# PSPS_AVNC_MITCH_2021-03-02.net
KiCad netlist of a schematic drawn in EAGLE
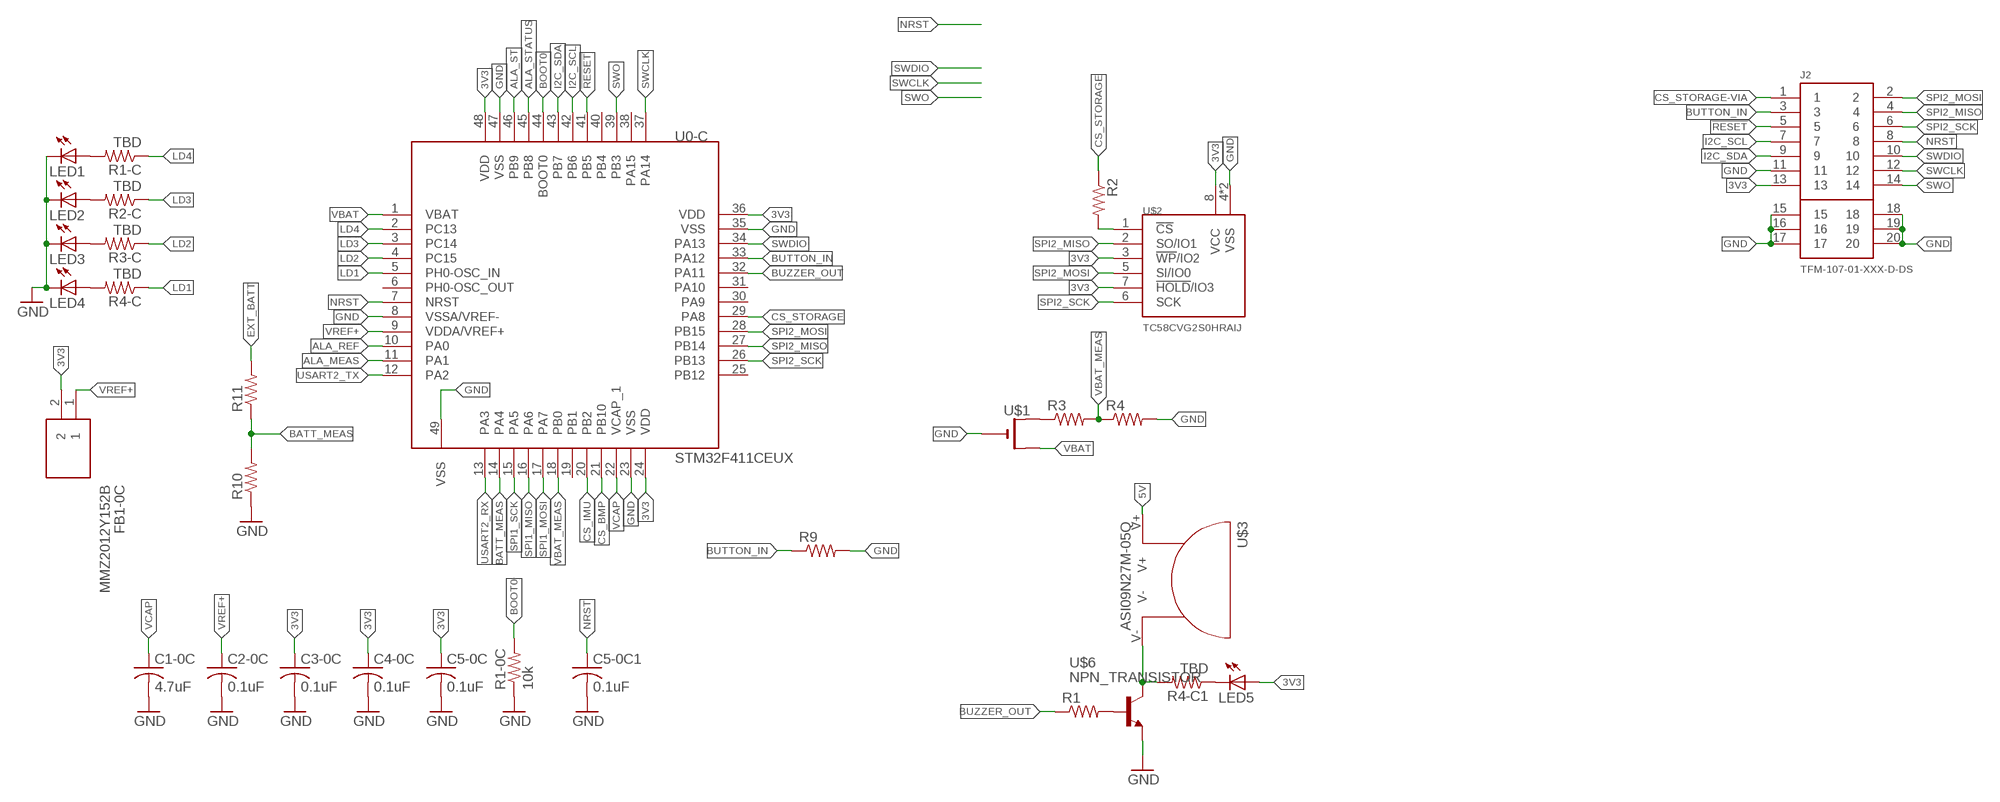
[diagram p0: schematic, sheet 1]
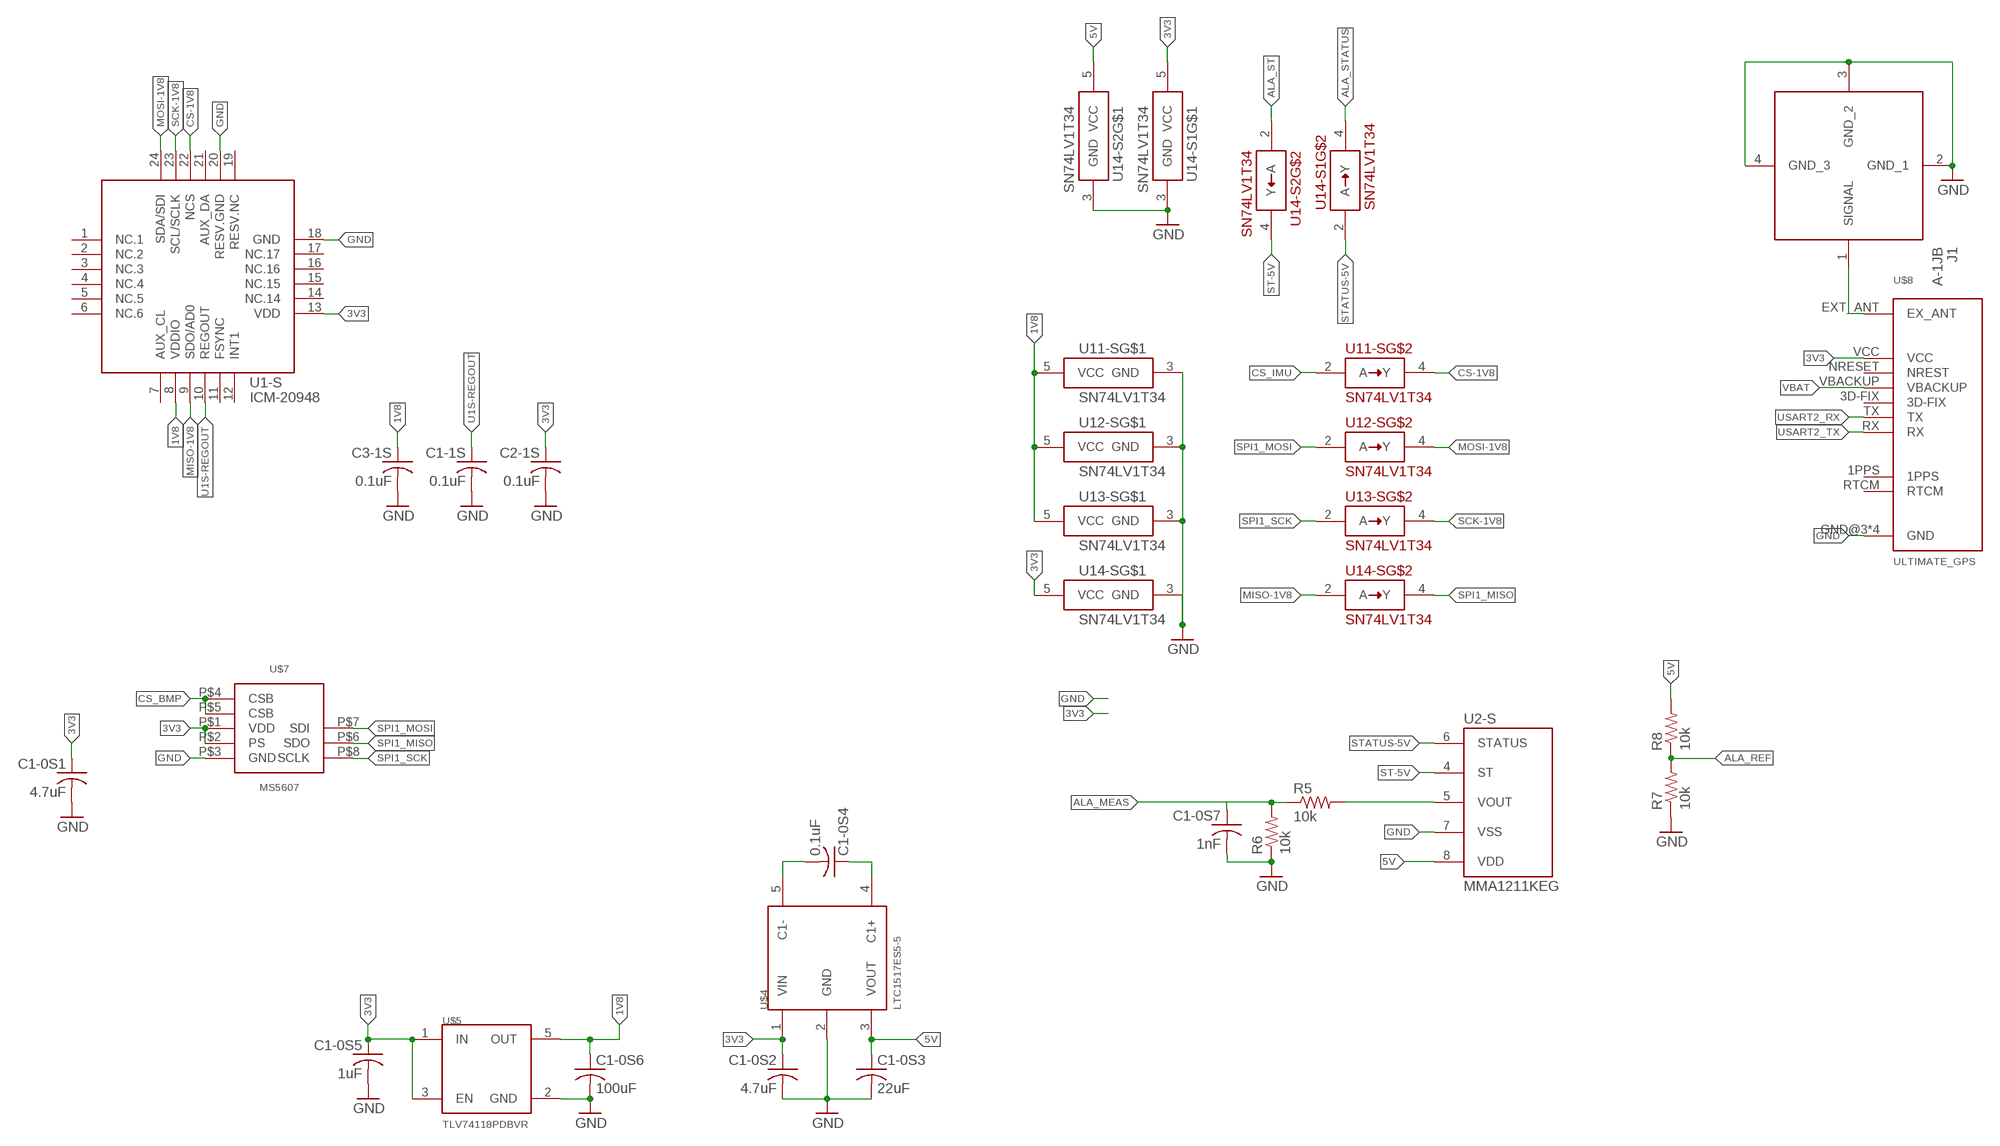
[diagram p1: schematic, sheet 2]

(export (version "E")
  (design (tool "Eeschema 10.0.6"))
  (components
    (comp (ref "C1-0S1")
      (value "4.7uF")
      (footprint "eagle-import:C0805")
      (libsource (lib "eagle-import") (part "C-USC0805"))
    )
    (comp (ref "C1-0S2")
      (value "4.7uF")
      (footprint "eagle-import:C0805")
      (libsource (lib "eagle-import") (part "C-USC0805"))
    )
    (comp (ref "C1-0S3")
      (value "22uF")
      (footprint "eagle-import:C0805")
      (libsource (lib "eagle-import") (part "C-USC0805"))
    )
    (comp (ref "C1-0S4")
      (value "0.1uF")
      (footprint "eagle-import:C0805")
      (libsource (lib "eagle-import") (part "C-USC0805"))
    )
    (comp (ref "C1-0S5")
      (value "1uF")
      (footprint "eagle-import:C0805")
      (libsource (lib "eagle-import") (part "C-USC0805"))
    )
    (comp (ref "C1-0S6")
      (value "100uF")
      (footprint "eagle-import:C0805")
      (libsource (lib "eagle-import") (part "C-USC0805"))
    )
    (comp (ref "C1-0S7")
      (value "1nF")
      (footprint "eagle-import:C0805")
      (libsource (lib "eagle-import") (part "C-USC0805"))
    )
    (comp (ref "C1-1S")
      (value "0.1uF")
      (footprint "eagle-import:C0805")
      (libsource (lib "eagle-import") (part "C-USC0805"))
    )
    (comp (ref "C2-1S")
      (value "0.1uF")
      (footprint "eagle-import:C0805")
      (libsource (lib "eagle-import") (part "C-USC0805"))
    )
    (comp (ref "C3-1S")
      (value "0.1uF")
      (footprint "eagle-import:C0805")
      (libsource (lib "eagle-import") (part "C-USC0805"))
    )
    (comp (ref "J1")
      (value "A-1JB")
      (footprint "eagle-import:A1JB")
      (fields (field (name "MOUSER_PART_NUMBER") "523-A-1JB"))
      (libsource (lib "eagle-import") (part "A-1JB"))
    )
    (comp (ref "R5")
      (value "10k")
      (footprint "eagle-import:R0805")
      (libsource (lib "eagle-import") (part "R-US_R0805"))
    )
    (comp (ref "R6")
      (value "10k")
      (footprint "eagle-import:R0805")
      (libsource (lib "eagle-import") (part "R-US_R0805"))
    )
    (comp (ref "R7")
      (value "10k")
      (footprint "eagle-import:R0805")
      (libsource (lib "eagle-import") (part "R-US_R0805"))
    )
    (comp (ref "R8")
      (value "10k")
      (footprint "eagle-import:R0805")
      (libsource (lib "eagle-import") (part "R-US_R0805"))
    )
    (comp (ref "U$4")
      (value "LTC1517ES5-5")
      (footprint "eagle-import:SOT95P280X145-5N")
      (libsource (lib "eagle-import") (part "LTC1517ES5-5"))
    )
    (comp (ref "U$5")
      (value "TLV74118PDBVR")
      (footprint "eagle-import:SOT95P280X145-5N")
      (libsource (lib "eagle-import") (part "TLV74118PDBVR"))
    )
    (comp (ref "U$7")
      (value "MS5607")
      (footprint "eagle-import:MS5607")
      (libsource (lib "eagle-import") (part "MS5607"))
    )
    (comp (ref "U$8")
      (value "ULTIMATE_GPS")
      (footprint "eagle-import:FGPMMOPA6H")
      (libsource (lib "eagle-import") (part "ULTIMATE_GPS"))
    )
    (comp (ref "U1-S")
      (value "ICM-20948")
      (footprint "eagle-import:QFN40P300X300X105-25T159X175")
      (libsource (lib "eagle-import") (part "ICM-20948"))
    )
    (comp (ref "U2-S")
      (value "MMA1211KEG")
      (footprint "eagle-import:SOIC127P1041X355-16N")
      (libsource (lib "eagle-import") (part "MMA1211KEG"))
    )
    (comp (ref "U11-S")
      (value "SN74LV1T34")
      (footprint "eagle-import:SOT65P210X110-5")
      (libsource (lib "eagle-import") (part "SN74LV1T34"))
    )
    (comp (ref "U12-S")
      (value "SN74LV1T34")
      (footprint "eagle-import:SOT65P210X110-5")
      (libsource (lib "eagle-import") (part "SN74LV1T34"))
    )
    (comp (ref "U13-S")
      (value "SN74LV1T34")
      (footprint "eagle-import:SOT65P210X110-5")
      (libsource (lib "eagle-import") (part "SN74LV1T34"))
    )
    (comp (ref "U14-S")
      (value "SN74LV1T34")
      (footprint "eagle-import:SOT65P210X110-5")
      (libsource (lib "eagle-import") (part "SN74LV1T34"))
    )
    (comp (ref "U14-S1")
      (value "SN74LV1T34")
      (footprint "eagle-import:SOT65P210X110-5")
      (libsource (lib "eagle-import") (part "SN74LV1T34"))
    )
    (comp (ref "U14-S2")
      (value "SN74LV1T34")
      (footprint "eagle-import:SOT65P210X110-5")
      (libsource (lib "eagle-import") (part "SN74LV1T34"))
    )
    (comp (ref "C1-0C")
      (value "4.7uF")
      (footprint "eagle-import:C0805")
      (libsource (lib "eagle-import") (part "C-USC0805"))
    )
    (comp (ref "C2-0C")
      (value "0.1uF")
      (footprint "eagle-import:C0805")
      (libsource (lib "eagle-import") (part "C-USC0805"))
    )
    (comp (ref "C3-0C")
      (value "0.1uF")
      (footprint "eagle-import:C0805")
      (libsource (lib "eagle-import") (part "C-USC0805"))
    )
    (comp (ref "C4-0C")
      (value "0.1uF")
      (footprint "eagle-import:C0805")
      (libsource (lib "eagle-import") (part "C-USC0805"))
    )
    (comp (ref "C5-0C")
      (value "0.1uF")
      (footprint "eagle-import:C0805")
      (libsource (lib "eagle-import") (part "C-USC0805"))
    )
    (comp (ref "C5-0C1")
      (value "0.1uF")
      (footprint "eagle-import:C0805")
      (libsource (lib "eagle-import") (part "C-USC0805"))
    )
    (comp (ref "FB1-0C")
      (value "MMZ2012Y152B")
      (footprint "eagle-import:BEADC2012X105N")
      (fields (field (name "MOUSER_PART_NUMBER") "810-MMZ2012Y152B"))
      (libsource (lib "eagle-import") (part "MMZ2012Y152B"))
    )
    (comp (ref "J2")
      (value "TFM-107-01-XXX-D-DS")
      (footprint "eagle-import:TFM-107-01-XXX-D-DS")
      (libsource (lib "eagle-import") (part "TFM-107-01-XXX-D-DS"))
    )
    (comp (ref "LED1")
      (value "LEDCHIPLED_0805")
      (footprint "eagle-import:CHIPLED_0805")
      (libsource (lib "eagle-import") (part "LEDCHIPLED_0805"))
    )
    (comp (ref "LED2")
      (value "LEDCHIPLED_0805")
      (footprint "eagle-import:CHIPLED_0805")
      (libsource (lib "eagle-import") (part "LEDCHIPLED_0805"))
    )
    (comp (ref "LED3")
      (value "LEDCHIPLED_0805")
      (footprint "eagle-import:CHIPLED_0805")
      (libsource (lib "eagle-import") (part "LEDCHIPLED_0805"))
    )
    (comp (ref "LED4")
      (value "LEDCHIPLED_0805")
      (footprint "eagle-import:CHIPLED_0805")
      (libsource (lib "eagle-import") (part "LEDCHIPLED_0805"))
    )
    (comp (ref "LED5")
      (value "LEDCHIPLED_0805")
      (footprint "eagle-import:CHIPLED_0805")
      (libsource (lib "eagle-import") (part "LEDCHIPLED_0805"))
    )
    (comp (ref "R1")
      (value "R-US_R0805")
      (footprint "eagle-import:R0805")
      (libsource (lib "eagle-import") (part "R-US_R0805"))
    )
    (comp (ref "R1-0C")
      (value "10k")
      (footprint "eagle-import:R0805")
      (libsource (lib "eagle-import") (part "R-US_R0805"))
    )
    (comp (ref "R1-C")
      (value "TBD")
      (footprint "eagle-import:R0805")
      (libsource (lib "eagle-import") (part "R-US_R0805"))
    )
    (comp (ref "R2")
      (value "R-US_R0805")
      (footprint "eagle-import:R0805")
      (libsource (lib "eagle-import") (part "R-US_R0805"))
    )
    (comp (ref "R2-C")
      (value "TBD")
      (footprint "eagle-import:R0805")
      (libsource (lib "eagle-import") (part "R-US_R0805"))
    )
    (comp (ref "R3")
      (value "R-US_R0805")
      (footprint "eagle-import:R0805")
      (libsource (lib "eagle-import") (part "R-US_R0805"))
    )
    (comp (ref "R3-C")
      (value "TBD")
      (footprint "eagle-import:R0805")
      (libsource (lib "eagle-import") (part "R-US_R0805"))
    )
    (comp (ref "R4")
      (value "R-US_R0805")
      (footprint "eagle-import:R0805")
      (libsource (lib "eagle-import") (part "R-US_R0805"))
    )
    (comp (ref "R4-C")
      (value "TBD")
      (footprint "eagle-import:R0805")
      (libsource (lib "eagle-import") (part "R-US_R0805"))
    )
    (comp (ref "R4-C1")
      (value "TBD")
      (footprint "eagle-import:R0805")
      (libsource (lib "eagle-import") (part "R-US_R0805"))
    )
    (comp (ref "R9")
      (value "R-US_R0805")
      (footprint "eagle-import:R0805")
      (libsource (lib "eagle-import") (part "R-US_R0805"))
    )
    (comp (ref "R10")
      (value "R-US_R0805")
      (footprint "eagle-import:R0805")
      (libsource (lib "eagle-import") (part "R-US_R0805"))
    )
    (comp (ref "R11")
      (value "R-US_R0805")
      (footprint "eagle-import:R0805")
      (libsource (lib "eagle-import") (part "R-US_R0805"))
    )
    (comp (ref "U$1")
      (value "CR1220SMT")
      (footprint "eagle-import:CR1220-SMD")
      (libsource (lib "eagle-import") (part "CR1220SMT"))
    )
    (comp (ref "U$2")
      (value "TC58CVG2S0HRAIJ")
      (footprint "eagle-import:SON127P800X600X80-9T350X440N")
      (libsource (lib "eagle-import") (part "TC58CVG2S0HRAIJ"))
    )
    (comp (ref "U$3")
      (value "ASI09N27M-05Q")
      (footprint "eagle-import:ASI09N27M-05Q")
      (libsource (lib "eagle-import") (part "ASI09N27M-05Q"))
    )
    (comp (ref "U$6")
      (value "NPN_TRANSISTOR")
      (footprint "eagle-import:SOT23")
      (libsource (lib "eagle-import") (part "NPN_TRANSISTOR"))
    )
    (comp (ref "U0-C")
      (value "STM32F411CEUX")
      (footprint "eagle-import:QFN50P700X700X50-49T560N")
      (libsource (lib "eagle-import") (part "STM32F411CEUX"))
    )
  )
  (nets
    (net (code "1") (name "1V8") (class "Default")
      (node (ref "C1-0S6") (pin "1") (pinfunction "1_1") (pintype "passive"))
      (node (ref "C3-1S") (pin "1") (pinfunction "1_1") (pintype "passive"))
      (node (ref "U$5") (pin "5") (pinfunction "OUT_5") (pintype "bidirectional"))
      (node (ref "U1-S") (pin "8") (pinfunction "VDDIO_8") (pintype "bidirectional"))
      (node (ref "U11-S") (pin "5") (pinfunction "VCC_5") (pintype "bidirectional"))
      (node (ref "U12-S") (pin "5") (pinfunction "VCC_5") (pintype "bidirectional"))
      (node (ref "U13-S") (pin "5") (pinfunction "VCC_5") (pintype "bidirectional"))
    )
    (net (code "2") (name "3V3") (class "Default")
      (node (ref "C1-0S1") (pin "1") (pinfunction "1_1") (pintype "passive"))
      (node (ref "C1-0S2") (pin "1") (pinfunction "1_1") (pintype "passive"))
      (node (ref "C1-0S5") (pin "1") (pinfunction "1_1") (pintype "passive"))
      (node (ref "C2-1S") (pin "1") (pinfunction "1_1") (pintype "passive"))
      (node (ref "C3-0C") (pin "1") (pinfunction "1_1") (pintype "passive"))
      (node (ref "C4-0C") (pin "1") (pinfunction "1_1") (pintype "passive"))
      (node (ref "C5-0C") (pin "1") (pinfunction "1_1") (pintype "passive"))
      (node (ref "FB1-0C") (pin "2") (pinfunction "2_2") (pintype "bidirectional"))
      (node (ref "J2") (pin "13") (pinfunction "13_13") (pintype "bidirectional"))
      (node (ref "LED5") (pin "A") (pinfunction "A_A") (pintype "passive"))
      (node (ref "U$2") (pin "3") (pinfunction "~{WP}/IO2_3") (pintype "bidirectional"))
      (node (ref "U$2") (pin "7") (pinfunction "~{HOLD}/IO3_7") (pintype "bidirectional"))
      (node (ref "U$2") (pin "8") (pinfunction "VCC_8") (pintype "bidirectional"))
      (node (ref "U$4") (pin "1") (pinfunction "VIN_1") (pintype "bidirectional"))
      (node (ref "U$5") (pin "1") (pinfunction "IN_1") (pintype "bidirectional"))
      (node (ref "U$5") (pin "3") (pinfunction "EN_3") (pintype "bidirectional"))
      (node (ref "U$7") (pin "P$1") (pinfunction "VDD_P$1") (pintype "bidirectional"))
      (node (ref "U$7") (pin "P$2") (pinfunction "PS_P$2") (pintype "bidirectional"))
      (node (ref "U$8") (pin "VCC") (pinfunction "VCC_VCC") (pintype "bidirectional"))
      (node (ref "U0-C") (pin "24") (pinfunction "VDD_24") (pintype "bidirectional"))
      (node (ref "U0-C") (pin "36") (pinfunction "VDD_36") (pintype "bidirectional"))
      (node (ref "U0-C") (pin "48") (pinfunction "VDD_48") (pintype "bidirectional"))
      (node (ref "U1-S") (pin "13") (pinfunction "VDD_13") (pintype "bidirectional"))
      (node (ref "U14-S") (pin "5") (pinfunction "VCC_5") (pintype "bidirectional"))
      (node (ref "U14-S1") (pin "5") (pinfunction "VCC_5") (pintype "bidirectional"))
    )
    (net (code "3") (name "5V") (class "Default")
      (node (ref "C1-0S3") (pin "1") (pinfunction "1_1") (pintype "passive"))
      (node (ref "R8") (pin "2") (pinfunction "2_2") (pintype "passive"))
      (node (ref "U$3") (pin "V+") (pinfunction "V+_V+") (pintype "bidirectional"))
      (node (ref "U$4") (pin "3") (pinfunction "VOUT_3") (pintype "bidirectional"))
      (node (ref "U14-S2") (pin "5") (pinfunction "VCC_5") (pintype "bidirectional"))
      (node (ref "U2-S") (pin "8") (pinfunction "VDD_8") (pintype "bidirectional"))
    )
    (net (code "4") (name "ALA_MEAS") (class "Default")
      (node (ref "C1-0S7") (pin "1") (pinfunction "1_1") (pintype "passive"))
      (node (ref "R5") (pin "1") (pinfunction "1_1") (pintype "passive"))
      (node (ref "R6") (pin "2") (pinfunction "2_2") (pintype "passive"))
      (node (ref "U0-C") (pin "11") (pinfunction "PA1_11") (pintype "bidirectional"))
    )
    (net (code "5") (name "ALA_REF") (class "Default")
      (node (ref "R7") (pin "2") (pinfunction "2_2") (pintype "passive"))
      (node (ref "R8") (pin "1") (pinfunction "1_1") (pintype "passive"))
      (node (ref "U0-C") (pin "10") (pinfunction "PA0_10") (pintype "bidirectional"))
    )
    (net (code "6") (name "ALA_ST") (class "Default")
      (node (ref "U0-C") (pin "46") (pinfunction "PB9_46") (pintype "bidirectional"))
      (node (ref "U14-S2") (pin "2") (pinfunction "A_2") (pintype "bidirectional"))
    )
    (net (code "7") (name "ALA_STATUS") (class "Default")
      (node (ref "U0-C") (pin "45") (pinfunction "PB8_45") (pintype "bidirectional"))
      (node (ref "U14-S1") (pin "4") (pinfunction "Y_4") (pintype "bidirectional"))
    )
    (net (code "8") (name "BATT_MEAS") (class "Default")
      (node (ref "R10") (pin "2") (pinfunction "2_2") (pintype "passive"))
      (node (ref "R11") (pin "1") (pinfunction "1_1") (pintype "passive"))
      (node (ref "U0-C") (pin "14") (pinfunction "PA4_14") (pintype "bidirectional"))
    )
    (net (code "9") (name "BOOT0") (class "Default")
      (node (ref "R1-0C") (pin "2") (pinfunction "2_2") (pintype "passive"))
      (node (ref "U0-C") (pin "44") (pinfunction "BOOT0_44") (pintype "bidirectional"))
    )
    (net (code "10") (name "BUTTON_IN") (class "Default")
      (node (ref "J2") (pin "3") (pinfunction "3_3") (pintype "bidirectional"))
      (node (ref "R9") (pin "1") (pinfunction "1_1") (pintype "passive"))
      (node (ref "U0-C") (pin "33") (pinfunction "PA12_33") (pintype "bidirectional"))
    )
    (net (code "11") (name "BUZZER_OUT") (class "Default")
      (node (ref "R1") (pin "1") (pinfunction "1_1") (pintype "passive"))
      (node (ref "U0-C") (pin "32") (pinfunction "PA11_32") (pintype "bidirectional"))
    )
    (net (code "12") (name "CS-1V8") (class "Default")
      (node (ref "U1-S") (pin "22") (pinfunction "NCS_22") (pintype "bidirectional"))
      (node (ref "U11-S") (pin "4") (pinfunction "Y_4") (pintype "bidirectional"))
    )
    (net (code "13") (name "CS_BMP") (class "Default")
      (node (ref "U$7") (pin "P$4") (pinfunction "CSB_P$4") (pintype "bidirectional"))
      (node (ref "U$7") (pin "P$5") (pinfunction "CSB_P$5") (pintype "bidirectional"))
      (node (ref "U0-C") (pin "21") (pinfunction "PB10_21") (pintype "bidirectional"))
    )
    (net (code "14") (name "CS_IMU") (class "Default")
      (node (ref "U0-C") (pin "20") (pinfunction "PB2_20") (pintype "bidirectional"))
      (node (ref "U11-S") (pin "2") (pinfunction "A_2") (pintype "bidirectional"))
    )
    (net (code "15") (name "CS_STORAGE") (class "Default")
      (node (ref "R2") (pin "1") (pinfunction "1_1") (pintype "passive"))
      (node (ref "U0-C") (pin "29") (pinfunction "PA8_29") (pintype "bidirectional"))
    )
    (net (code "16") (name "CS_STORAGE-VIA") (class "Default")
      (node (ref "J2") (pin "1") (pinfunction "1_1") (pintype "bidirectional"))
      (node (ref "R2") (pin "2") (pinfunction "2_2") (pintype "passive"))
      (node (ref "U$2") (pin "1") (pinfunction "~{CS}_1") (pintype "bidirectional"))
    )
    (net (code "17") (name "EXT_BATT") (class "Default")
      (node (ref "R11") (pin "2") (pinfunction "2_2") (pintype "passive"))
    )
    (net (code "18") (name "GND") (class "Default")
      (node (ref "C1-0C") (pin "2") (pinfunction "2_2") (pintype "passive"))
      (node (ref "C1-0S1") (pin "2") (pinfunction "2_2") (pintype "passive"))
      (node (ref "C1-0S2") (pin "2") (pinfunction "2_2") (pintype "passive"))
      (node (ref "C1-0S3") (pin "2") (pinfunction "2_2") (pintype "passive"))
      (node (ref "C1-0S5") (pin "2") (pinfunction "2_2") (pintype "passive"))
      (node (ref "C1-0S6") (pin "2") (pinfunction "2_2") (pintype "passive"))
      (node (ref "C1-0S7") (pin "2") (pinfunction "2_2") (pintype "passive"))
      (node (ref "C1-1S") (pin "2") (pinfunction "2_2") (pintype "passive"))
      (node (ref "C2-0C") (pin "2") (pinfunction "2_2") (pintype "passive"))
      (node (ref "C2-1S") (pin "2") (pinfunction "2_2") (pintype "passive"))
      (node (ref "C3-0C") (pin "2") (pinfunction "2_2") (pintype "passive"))
      (node (ref "C3-1S") (pin "2") (pinfunction "2_2") (pintype "passive"))
      (node (ref "C4-0C") (pin "2") (pinfunction "2_2") (pintype "passive"))
      (node (ref "C5-0C") (pin "2") (pinfunction "2_2") (pintype "passive"))
      (node (ref "C5-0C1") (pin "2") (pinfunction "2_2") (pintype "passive"))
      (node (ref "J1") (pin "2") (pinfunction "GND_1_2") (pintype "bidirectional"))
      (node (ref "J1") (pin "3") (pinfunction "GND_2_3") (pintype "bidirectional"))
      (node (ref "J1") (pin "4") (pinfunction "GND_3_4") (pintype "bidirectional"))
      (node (ref "J2") (pin "11") (pinfunction "11_11") (pintype "bidirectional"))
      (node (ref "J2") (pin "15") (pinfunction "15_15") (pintype "bidirectional"))
      (node (ref "J2") (pin "16") (pinfunction "16_16") (pintype "bidirectional"))
      (node (ref "J2") (pin "17") (pinfunction "17_17") (pintype "bidirectional"))
      (node (ref "J2") (pin "18") (pinfunction "18_18") (pintype "bidirectional"))
      (node (ref "J2") (pin "19") (pinfunction "19_19") (pintype "bidirectional"))
      (node (ref "J2") (pin "20") (pinfunction "20_20") (pintype "bidirectional"))
      (node (ref "LED1") (pin "C") (pinfunction "C_C") (pintype "passive"))
      (node (ref "LED2") (pin "C") (pinfunction "C_C") (pintype "passive"))
      (node (ref "LED3") (pin "C") (pinfunction "C_C") (pintype "passive"))
      (node (ref "LED4") (pin "C") (pinfunction "C_C") (pintype "passive"))
      (node (ref "R1-0C") (pin "1") (pinfunction "1_1") (pintype "passive"))
      (node (ref "R10") (pin "1") (pinfunction "1_1") (pintype "passive"))
      (node (ref "R4") (pin "2") (pinfunction "2_2") (pintype "passive"))
      (node (ref "R6") (pin "1") (pinfunction "1_1") (pintype "passive"))
      (node (ref "R7") (pin "1") (pinfunction "1_1") (pintype "passive"))
      (node (ref "R9") (pin "2") (pinfunction "2_2") (pintype "passive"))
      (node (ref "U$1") (pin "-") (pinfunction "-_-") (pintype "passive"))
      (node (ref "U$2") (pin "4") (pinfunction "VSS_4") (pintype "bidirectional"))
      (node (ref "U$2") (pin "9") (pinfunction "VSS_9") (pintype "bidirectional"))
      (node (ref "U$4") (pin "2") (pinfunction "GND_2") (pintype "bidirectional"))
      (node (ref "U$5") (pin "2") (pinfunction "GND_2") (pintype "bidirectional"))
      (node (ref "U$6") (pin "3") (pinfunction "E_3") (pintype "passive"))
      (node (ref "U$7") (pin "P$3") (pinfunction "GND_P$3") (pintype "bidirectional"))
      (node (ref "U$8") (pin "GND@12") (pinfunction "GND_GND@12") (pintype "bidirectional"))
      (node (ref "U$8") (pin "GND@19") (pinfunction "GND_GND@19") (pintype "bidirectional"))
      (node (ref "U$8") (pin "GND@3") (pinfunction "GND_GND@3") (pintype "bidirectional"))
      (node (ref "U$8") (pin "GND@8") (pinfunction "GND_GND@8") (pintype "bidirectional"))
      (node (ref "U0-C") (pin "23") (pinfunction "VSS_23") (pintype "bidirectional"))
      (node (ref "U0-C") (pin "35") (pinfunction "VSS_35") (pintype "bidirectional"))
      (node (ref "U0-C") (pin "47") (pinfunction "VSS_47") (pintype "bidirectional"))
      (node (ref "U0-C") (pin "49") (pinfunction "VSS_49") (pintype "bidirectional"))
      (node (ref "U0-C") (pin "8") (pinfunction "VSSA/VREF-_8") (pintype "bidirectional"))
      (node (ref "U1-S") (pin "18") (pinfunction "GND_18") (pintype "bidirectional"))
      (node (ref "U1-S") (pin "20") (pinfunction "RESV.GND_20") (pintype "bidirectional"))
      (node (ref "U11-S") (pin "3") (pinfunction "GND_3") (pintype "bidirectional"))
      (node (ref "U12-S") (pin "3") (pinfunction "GND_3") (pintype "bidirectional"))
      (node (ref "U13-S") (pin "3") (pinfunction "GND_3") (pintype "bidirectional"))
      (node (ref "U14-S") (pin "3") (pinfunction "GND_3") (pintype "bidirectional"))
      (node (ref "U14-S1") (pin "3") (pinfunction "GND_3") (pintype "bidirectional"))
      (node (ref "U14-S2") (pin "3") (pinfunction "GND_3") (pintype "bidirectional"))
      (node (ref "U2-S") (pin "7") (pinfunction "VSS_7") (pintype "bidirectional"))
    )
    (net (code "19") (name "I2C_SCL") (class "Default")
      (node (ref "J2") (pin "7") (pinfunction "7_7") (pintype "bidirectional"))
      (node (ref "U0-C") (pin "42") (pinfunction "PB6_42") (pintype "bidirectional"))
    )
    (net (code "20") (name "I2C_SDA") (class "Default")
      (node (ref "J2") (pin "9") (pinfunction "9_9") (pintype "bidirectional"))
      (node (ref "U0-C") (pin "43") (pinfunction "PB7_43") (pintype "bidirectional"))
    )
    (net (code "21") (name "LD1") (class "Default")
      (node (ref "R4-C") (pin "1") (pinfunction "1_1") (pintype "passive"))
      (node (ref "U0-C") (pin "5") (pinfunction "PH0-OSC_IN_5") (pintype "bidirectional"))
    )
    (net (code "22") (name "LD2") (class "Default")
      (node (ref "R3-C") (pin "1") (pinfunction "1_1") (pintype "passive"))
      (node (ref "U0-C") (pin "4") (pinfunction "PC15_4") (pintype "bidirectional"))
    )
    (net (code "23") (name "LD3") (class "Default")
      (node (ref "R2-C") (pin "1") (pinfunction "1_1") (pintype "passive"))
      (node (ref "U0-C") (pin "3") (pinfunction "PC14_3") (pintype "bidirectional"))
    )
    (net (code "24") (name "LD4") (class "Default")
      (node (ref "R1-C") (pin "1") (pinfunction "1_1") (pintype "passive"))
      (node (ref "U0-C") (pin "2") (pinfunction "PC13_2") (pintype "bidirectional"))
    )
    (net (code "25") (name "MISO-1V8") (class "Default")
      (node (ref "U1-S") (pin "9") (pinfunction "SDO/AD0_9") (pintype "bidirectional"))
      (node (ref "U14-S") (pin "2") (pinfunction "A_2") (pintype "bidirectional"))
    )
    (net (code "26") (name "MOSI-1V8") (class "Default")
      (node (ref "U1-S") (pin "24") (pinfunction "SDA/SDI_24") (pintype "bidirectional"))
      (node (ref "U12-S") (pin "4") (pinfunction "Y_4") (pintype "bidirectional"))
    )
    (net (code "27") (name "NRST") (class "Default")
      (node (ref "C5-0C1") (pin "1") (pinfunction "1_1") (pintype "passive"))
      (node (ref "J2") (pin "8") (pinfunction "8_8") (pintype "bidirectional"))
      (node (ref "U0-C") (pin "7") (pinfunction "NRST_7") (pintype "bidirectional"))
    )
    (net (code "28") (name "Net-(J1-SIGNAL)") (class "Default")
      (node (ref "J1") (pin "1") (pinfunction "SIGNAL_1") (pintype "bidirectional"))
      (node (ref "U$8") (pin "EXT_ANT") (pinfunction "EX_ANT_EXT_ANT") (pintype "bidirectional"))
    )
    (net (code "29") (name "Net-(LED1-PadA)") (class "Default")
      (node (ref "LED1") (pin "A") (pinfunction "A_A") (pintype "passive"))
      (node (ref "R1-C") (pin "2") (pinfunction "2_2") (pintype "passive"))
    )
    (net (code "30") (name "Net-(LED2-PadA)") (class "Default")
      (node (ref "LED2") (pin "A") (pinfunction "A_A") (pintype "passive"))
      (node (ref "R2-C") (pin "2") (pinfunction "2_2") (pintype "passive"))
    )
    (net (code "31") (name "Net-(LED3-PadA)") (class "Default")
      (node (ref "LED3") (pin "A") (pinfunction "A_A") (pintype "passive"))
      (node (ref "R3-C") (pin "2") (pinfunction "2_2") (pintype "passive"))
    )
    (net (code "32") (name "Net-(LED4-PadA)") (class "Default")
      (node (ref "LED4") (pin "A") (pinfunction "A_A") (pintype "passive"))
      (node (ref "R4-C") (pin "2") (pinfunction "2_2") (pintype "passive"))
    )
    (net (code "33") (name "Net-(LED5-PadC)") (class "Default")
      (node (ref "LED5") (pin "C") (pinfunction "C_C") (pintype "passive"))
      (node (ref "R4-C1") (pin "1") (pinfunction "1_1") (pintype "passive"))
    )
    (net (code "34") (name "Net-(U$1-+)") (class "Default")
      (node (ref "R3") (pin "1") (pinfunction "1_1") (pintype "passive"))
      (node (ref "U$1") (pin "+$1") (pinfunction "+_+$1") (pintype "passive"))
    )
    (net (code "35") (name "Net-(U$4-C1+)") (class "Default")
      (node (ref "C1-0S4") (pin "1") (pinfunction "1_1") (pintype "passive"))
      (node (ref "U$4") (pin "4") (pinfunction "C1+_4") (pintype "bidirectional"))
    )
    (net (code "36") (name "Net-(U$4-C1-)") (class "Default")
      (node (ref "C1-0S4") (pin "2") (pinfunction "2_2") (pintype "passive"))
      (node (ref "U$4") (pin "5") (pinfunction "C1-_5") (pintype "bidirectional"))
    )
    (net (code "37") (name "Net-(U$6-B)") (class "Default")
      (node (ref "R1") (pin "2") (pinfunction "2_2") (pintype "passive"))
      (node (ref "U$6") (pin "1") (pinfunction "B_1") (pintype "passive"))
    )
    (net (code "38") (name "Net-(U$6-C)") (class "Default")
      (node (ref "R4-C1") (pin "2") (pinfunction "2_2") (pintype "passive"))
      (node (ref "U$3") (pin "V-") (pinfunction "V-_V-") (pintype "bidirectional"))
      (node (ref "U$6") (pin "2") (pinfunction "C_2") (pintype "passive"))
    )
    (net (code "39") (name "Net-(U2-S-VOUT)") (class "Default")
      (node (ref "R5") (pin "2") (pinfunction "2_2") (pintype "passive"))
      (node (ref "U2-S") (pin "5") (pinfunction "VOUT_5") (pintype "bidirectional"))
    )
    (net (code "40") (name "SCK-1V8") (class "Default")
      (node (ref "U1-S") (pin "23") (pinfunction "SCL/SCLK_23") (pintype "bidirectional"))
      (node (ref "U13-S") (pin "4") (pinfunction "Y_4") (pintype "bidirectional"))
    )
    (net (code "41") (name "SPI1_MISO") (class "Default")
      (node (ref "U$7") (pin "P$6") (pinfunction "SDO_P$6") (pintype "bidirectional"))
      (node (ref "U0-C") (pin "16") (pinfunction "PA6_16") (pintype "bidirectional"))
      (node (ref "U14-S") (pin "4") (pinfunction "Y_4") (pintype "bidirectional"))
    )
    (net (code "42") (name "SPI1_MOSI") (class "Default")
      (node (ref "U$7") (pin "P$7") (pinfunction "SDI_P$7") (pintype "bidirectional"))
      (node (ref "U0-C") (pin "17") (pinfunction "PA7_17") (pintype "bidirectional"))
      (node (ref "U12-S") (pin "2") (pinfunction "A_2") (pintype "bidirectional"))
    )
    (net (code "43") (name "SPI1_SCK") (class "Default")
      (node (ref "U$7") (pin "P$8") (pinfunction "SCLK_P$8") (pintype "bidirectional"))
      (node (ref "U0-C") (pin "15") (pinfunction "PA5_15") (pintype "bidirectional"))
      (node (ref "U13-S") (pin "2") (pinfunction "A_2") (pintype "bidirectional"))
    )
    (net (code "44") (name "SPI2_MISO") (class "Default")
      (node (ref "J2") (pin "4") (pinfunction "4_4") (pintype "bidirectional"))
      (node (ref "U$2") (pin "2") (pinfunction "SO/IO1_2") (pintype "bidirectional"))
      (node (ref "U0-C") (pin "27") (pinfunction "PB14_27") (pintype "bidirectional"))
    )
    (net (code "45") (name "SPI2_MOSI") (class "Default")
      (node (ref "J2") (pin "2") (pinfunction "2_2") (pintype "bidirectional"))
      (node (ref "U$2") (pin "5") (pinfunction "SI/IO0_5") (pintype "bidirectional"))
      (node (ref "U0-C") (pin "28") (pinfunction "PB15_28") (pintype "bidirectional"))
    )
    (net (code "46") (name "SPI2_SCK") (class "Default")
      (node (ref "J2") (pin "6") (pinfunction "6_6") (pintype "bidirectional"))
      (node (ref "U$2") (pin "6") (pinfunction "SCK_6") (pintype "bidirectional"))
      (node (ref "U0-C") (pin "26") (pinfunction "PB13_26") (pintype "bidirectional"))
    )
    (net (code "47") (name "ST-5V") (class "Default")
      (node (ref "U14-S2") (pin "4") (pinfunction "Y_4") (pintype "bidirectional"))
      (node (ref "U2-S") (pin "4") (pinfunction "ST_4") (pintype "bidirectional"))
    )
    (net (code "48") (name "STATUS-5V") (class "Default")
      (node (ref "U14-S1") (pin "2") (pinfunction "A_2") (pintype "bidirectional"))
      (node (ref "U2-S") (pin "6") (pinfunction "STATUS_6") (pintype "bidirectional"))
    )
    (net (code "49") (name "SWCLK") (class "Default")
      (node (ref "J2") (pin "12") (pinfunction "12_12") (pintype "bidirectional"))
      (node (ref "U0-C") (pin "37") (pinfunction "PA14_37") (pintype "bidirectional"))
    )
    (net (code "50") (name "SWDIO") (class "Default")
      (node (ref "J2") (pin "10") (pinfunction "10_10") (pintype "bidirectional"))
      (node (ref "U0-C") (pin "34") (pinfunction "PA13_34") (pintype "bidirectional"))
    )
    (net (code "51") (name "SWO") (class "Default")
      (node (ref "J2") (pin "14") (pinfunction "14_14") (pintype "bidirectional"))
      (node (ref "U0-C") (pin "39") (pinfunction "PB3_39") (pintype "bidirectional"))
    )
    (net (code "52") (name "U1S-REGOUT") (class "Default")
      (node (ref "C1-1S") (pin "1") (pinfunction "1_1") (pintype "passive"))
      (node (ref "U1-S") (pin "10") (pinfunction "REGOUT_10") (pintype "bidirectional"))
    )
    (net (code "53") (name "USART2_RX") (class "Default")
      (node (ref "U$8") (pin "TX") (pinfunction "TX_TX") (pintype "bidirectional"))
      (node (ref "U0-C") (pin "13") (pinfunction "PA3_13") (pintype "bidirectional"))
    )
    (net (code "54") (name "USART2_TX") (class "Default")
      (node (ref "U$8") (pin "RX") (pinfunction "RX_RX") (pintype "bidirectional"))
      (node (ref "U0-C") (pin "12") (pinfunction "PA2_12") (pintype "bidirectional"))
    )
    (net (code "55") (name "VBAT") (class "Default")
      (node (ref "U$1") (pin "+$2") (pinfunction "+1_+$2") (pintype "passive"))
      (node (ref "U$8") (pin "VBACKUP") (pinfunction "VBACKUP_VBACKUP") (pintype "bidirectional"))
      (node (ref "U0-C") (pin "1") (pinfunction "VBAT_1") (pintype "bidirectional"))
    )
    (net (code "56") (name "VBAT_MEAS") (class "Default")
      (node (ref "R3") (pin "2") (pinfunction "2_2") (pintype "passive"))
      (node (ref "R4") (pin "1") (pinfunction "1_1") (pintype "passive"))
      (node (ref "U0-C") (pin "18") (pinfunction "PB0_18") (pintype "bidirectional"))
    )
    (net (code "57") (name "VCAP") (class "Default")
      (node (ref "C1-0C") (pin "1") (pinfunction "1_1") (pintype "passive"))
      (node (ref "U0-C") (pin "22") (pinfunction "VCAP_1_22") (pintype "bidirectional"))
    )
    (net (code "58") (name "VREF+") (class "Default")
      (node (ref "C2-0C") (pin "1") (pinfunction "1_1") (pintype "passive"))
      (node (ref "FB1-0C") (pin "1") (pinfunction "1_1") (pintype "bidirectional"))
      (node (ref "U0-C") (pin "9") (pinfunction "VDDA/VREF+_9") (pintype "bidirectional"))
    )
    (net (code "59") (name "unconnected-(U$8-NREST-PadNRESET)") (class "Default")
      (node (ref "U$8") (pin "NRESET") (pinfunction "NREST_NRESET") (pintype "bidirectional"))
    )
    (net (code "60") (name "unconnected-(U$8-Pad1PPS)") (class "Default")
      (node (ref "U$8") (pin "1PPS") (pinfunction "1PPS_1PPS") (pintype "bidirectional"))
    )
    (net (code "61") (name "unconnected-(U$8-Pad3D-FIX)") (class "Default")
      (node (ref "U$8") (pin "3D-FIX") (pinfunction "3D-FIX_3D-FIX") (pintype "bidirectional"))
    )
    (net (code "62") (name "unconnected-(U$8-PadRTCM)") (class "Default")
      (node (ref "U$8") (pin "RTCM") (pinfunction "RTCM_RTCM") (pintype "bidirectional"))
    )
    (net (code "63") (name "unconnected-(U0-C-PA9-Pad30)") (class "Default")
      (node (ref "U0-C") (pin "30") (pinfunction "PA9_30") (pintype "bidirectional"))
    )
    (net (code "64") (name "unconnected-(U0-C-PA10-Pad31)") (class "Default")
      (node (ref "U0-C") (pin "31") (pinfunction "PA10_31") (pintype "bidirectional"))
    )
    (net (code "65") (name "unconnected-(U0-C-PA15-Pad38)") (class "Default")
      (node (ref "U0-C") (pin "38") (pinfunction "PA15_38") (pintype "bidirectional"))
    )
    (net (code "66") (name "unconnected-(U0-C-PB1-Pad19)") (class "Default")
      (node (ref "U0-C") (pin "19") (pinfunction "PB1_19") (pintype "bidirectional"))
    )
    (net (code "67") (name "unconnected-(U0-C-PB4-Pad40)") (class "Default")
      (node (ref "U0-C") (pin "40") (pinfunction "PB4_40") (pintype "bidirectional"))
    )
    (net (code "68") (name "unconnected-(U0-C-PB12-Pad25)") (class "Default")
      (node (ref "U0-C") (pin "25") (pinfunction "PB12_25") (pintype "bidirectional"))
    )
    (net (code "69") (name "unconnected-(U0-C-PH0-OSC_OUT-Pad6)") (class "Default")
      (node (ref "U0-C") (pin "6") (pinfunction "PH0-OSC_OUT_6") (pintype "bidirectional"))
    )
    (net (code "70") (name "unconnected-(U1-S-AUX_CL-Pad7)") (class "Default")
      (node (ref "U1-S") (pin "7") (pinfunction "AUX_CL_7") (pintype "bidirectional"))
    )
    (net (code "71") (name "unconnected-(U1-S-AUX_DA-Pad21)") (class "Default")
      (node (ref "U1-S") (pin "21") (pinfunction "AUX_DA_21") (pintype "bidirectional"))
    )
    (net (code "72") (name "unconnected-(U1-S-FSYNC-Pad11)") (class "Default")
      (node (ref "U1-S") (pin "11") (pinfunction "FSYNC_11") (pintype "bidirectional"))
    )
    (net (code "73") (name "unconnected-(U1-S-INT1-Pad12)") (class "Default")
      (node (ref "U1-S") (pin "12") (pinfunction "INT1_12") (pintype "bidirectional"))
    )
    (net (code "74") (name "unconnected-(U1-S-NC.1-Pad1)") (class "Default")
      (node (ref "U1-S") (pin "1") (pinfunction "NC.1_1") (pintype "bidirectional"))
    )
    (net (code "75") (name "unconnected-(U1-S-NC.2-Pad2)") (class "Default")
      (node (ref "U1-S") (pin "2") (pinfunction "NC.2_2") (pintype "bidirectional"))
    )
    (net (code "76") (name "unconnected-(U1-S-NC.3-Pad3)") (class "Default")
      (node (ref "U1-S") (pin "3") (pinfunction "NC.3_3") (pintype "bidirectional"))
    )
    (net (code "77") (name "unconnected-(U1-S-NC.4-Pad4)") (class "Default")
      (node (ref "U1-S") (pin "4") (pinfunction "NC.4_4") (pintype "bidirectional"))
    )
    (net (code "78") (name "unconnected-(U1-S-NC.5-Pad5)") (class "Default")
      (node (ref "U1-S") (pin "5") (pinfunction "NC.5_5") (pintype "bidirectional"))
    )
    (net (code "79") (name "unconnected-(U1-S-NC.6-Pad6)") (class "Default")
      (node (ref "U1-S") (pin "6") (pinfunction "NC.6_6") (pintype "bidirectional"))
    )
    (net (code "80") (name "unconnected-(U1-S-NC.14-Pad14)") (class "Default")
      (node (ref "U1-S") (pin "14") (pinfunction "NC.14_14") (pintype "bidirectional"))
    )
    (net (code "81") (name "unconnected-(U1-S-NC.15-Pad15)") (class "Default")
      (node (ref "U1-S") (pin "15") (pinfunction "NC.15_15") (pintype "bidirectional"))
    )
    (net (code "82") (name "unconnected-(U1-S-NC.16-Pad16)") (class "Default")
      (node (ref "U1-S") (pin "16") (pinfunction "NC.16_16") (pintype "bidirectional"))
    )
    (net (code "83") (name "unconnected-(U1-S-NC.17-Pad17)") (class "Default")
      (node (ref "U1-S") (pin "17") (pinfunction "NC.17_17") (pintype "bidirectional"))
    )
    (net (code "84") (name "unconnected-(U1-S-RESV.NC-Pad19)") (class "Default")
      (node (ref "U1-S") (pin "19") (pinfunction "RESV.NC_19") (pintype "bidirectional"))
    )
    (net (code "85") (name "~{RESET}") (class "Default")
      (node (ref "J2") (pin "5") (pinfunction "5_5") (pintype "bidirectional"))
      (node (ref "U0-C") (pin "41") (pinfunction "PB5_41") (pintype "bidirectional"))
    )
  )
)
